# MAZ000174_-_Diagrama_el_ctrico.net
KiCad netlist of a schematic drawn in Altium Designer
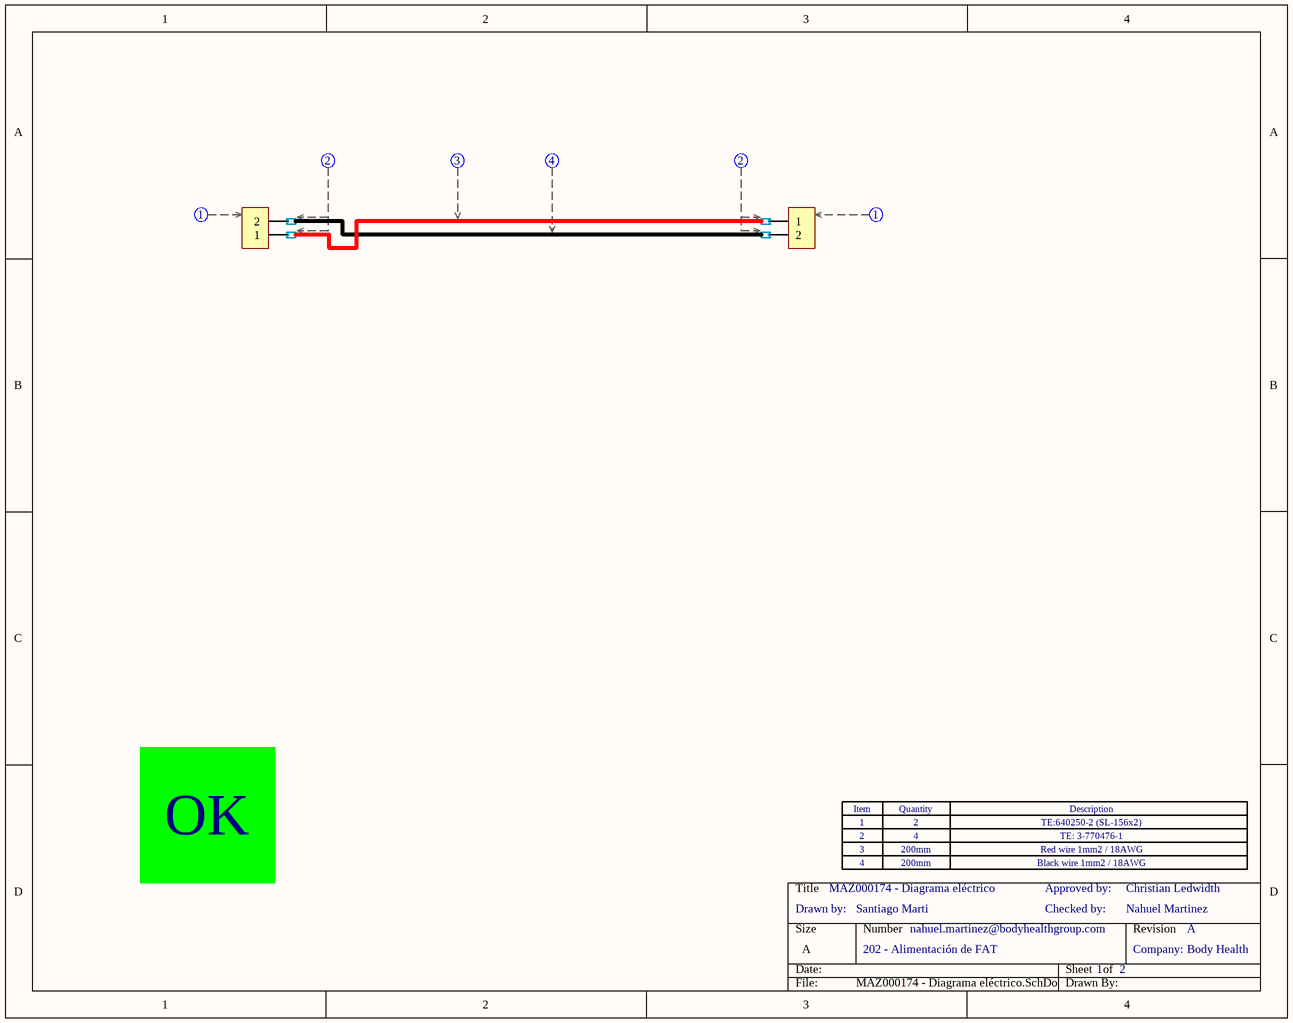
[diagram p0: MAZ000174 - Diagrama eléctrico.SchDoc]

(export (version "E")
  (design (tool "Eeschema 10.0.6"))
  (components
    (comp (ref "Con1")
      (value "SL156-2")
      (description "CONN RECEPT 2 POS W/RAMP SL-156")
      (libsource (lib "") (part "SL156-2_2"))
    )
    (comp (ref "Con2")
      (value "SL156-2")
      (description "CONN RECEPT 2 POS W/RAMP SL-156")
      (libsource (lib "") (part "SL156-2_2"))
    )
    (comp (ref "Soc1")
      (value "sock_SL156_770476-1")
      (description "CONN SOCKET 18-24AWG CRIMP TIN")
      (libsource (lib "LibreriaParaPlanos") (part "sock_SL156_770476-1"))
    )
    (comp (ref "Soc2")
      (value "sock_SL156_770476-1")
      (description "CONN SOCKET 18-24AWG CRIMP TIN")
      (libsource (lib "LibreriaParaPlanos") (part "sock_SL156_770476-1"))
    )
    (comp (ref "Soc3")
      (value "sock_SL156_770476-1")
      (description "CONN SOCKET 18-24AWG CRIMP TIN")
      (libsource (lib "LibreriaParaPlanos") (part "sock_SL156_770476-1"))
    )
    (comp (ref "Soc4")
      (value "sock_SL156_770476-1")
      (description "CONN SOCKET 18-24AWG CRIMP TIN")
      (libsource (lib "LibreriaParaPlanos") (part "sock_SL156_770476-1"))
    )
    (comp (ref "Zoc1")
      (value "Zócalo_Header")
      (description "Header para el zócalo de referencias")
      (libsource (lib "LibreriaParaPlanos") (part "Zócalo_Header"))
    )
    (comp (ref "Zoc2")
      (value "Zócalo_Item")
      (description "Ítem para el zócalo de referencias")
      (libsource (lib "LibreriaParaPlanos") (part "Zócalo_Item"))
    )
    (comp (ref "Zoc3")
      (value "Zócalo_Item")
      (description "Ítem para el zócalo de referencias")
      (libsource (lib "LibreriaParaPlanos") (part "Zócalo_Item"))
    )
    (comp (ref "Zoc4")
      (value "Zócalo_Item")
      (description "Ítem para el zócalo de referencias")
      (libsource (lib "LibreriaParaPlanos") (part "Zócalo_Item"))
    )
    (comp (ref "Zoc5")
      (value "Zócalo_Item")
      (description "Ítem para el zócalo de referencias")
      (libsource (lib "LibreriaParaPlanos") (part "Zócalo_Item"))
    )
  )
  (nets
    (net (code "1") (name "Net-(Con1-Pad1)") (class "Default")
      (node (ref "Con1") (pin "1") (pinfunction "1_1") (pintype "passive"))
      (node (ref "Soc3") (pin "0") (pinfunction "0_0") (pintype "passive"))
    )
    (net (code "2") (name "Net-(Con1-Pad2)") (class "Default")
      (node (ref "Con1") (pin "2") (pinfunction "2_2") (pintype "passive"))
      (node (ref "Soc1") (pin "0") (pinfunction "0_0") (pintype "passive"))
    )
    (net (code "3") (name "Net-(Con2-Pad1)") (class "Default")
      (node (ref "Con2") (pin "1") (pinfunction "1_1") (pintype "passive"))
      (node (ref "Soc2") (pin "0") (pinfunction "0_0") (pintype "passive"))
    )
    (net (code "4") (name "Net-(Con2-Pad2)") (class "Default")
      (node (ref "Con2") (pin "2") (pinfunction "2_2") (pintype "passive"))
      (node (ref "Soc4") (pin "0") (pinfunction "0_0") (pintype "passive"))
    )
    (net (code "5") (name "Net-(Soc1-Pad1)") (class "Default")
      (node (ref "Soc1") (pin "1") (pinfunction "1_1") (pintype "passive"))
      (node (ref "Soc4") (pin "1") (pinfunction "1_1") (pintype "passive"))
    )
    (net (code "6") (name "Net-(Soc2-Pad1)") (class "Default")
      (node (ref "Soc2") (pin "1") (pinfunction "1_1") (pintype "passive"))
      (node (ref "Soc3") (pin "1") (pinfunction "1_1") (pintype "passive"))
    )
  )
)
